# FAL65816_6567a.net
KiCad netlist of a schematic drawn in EAGLE
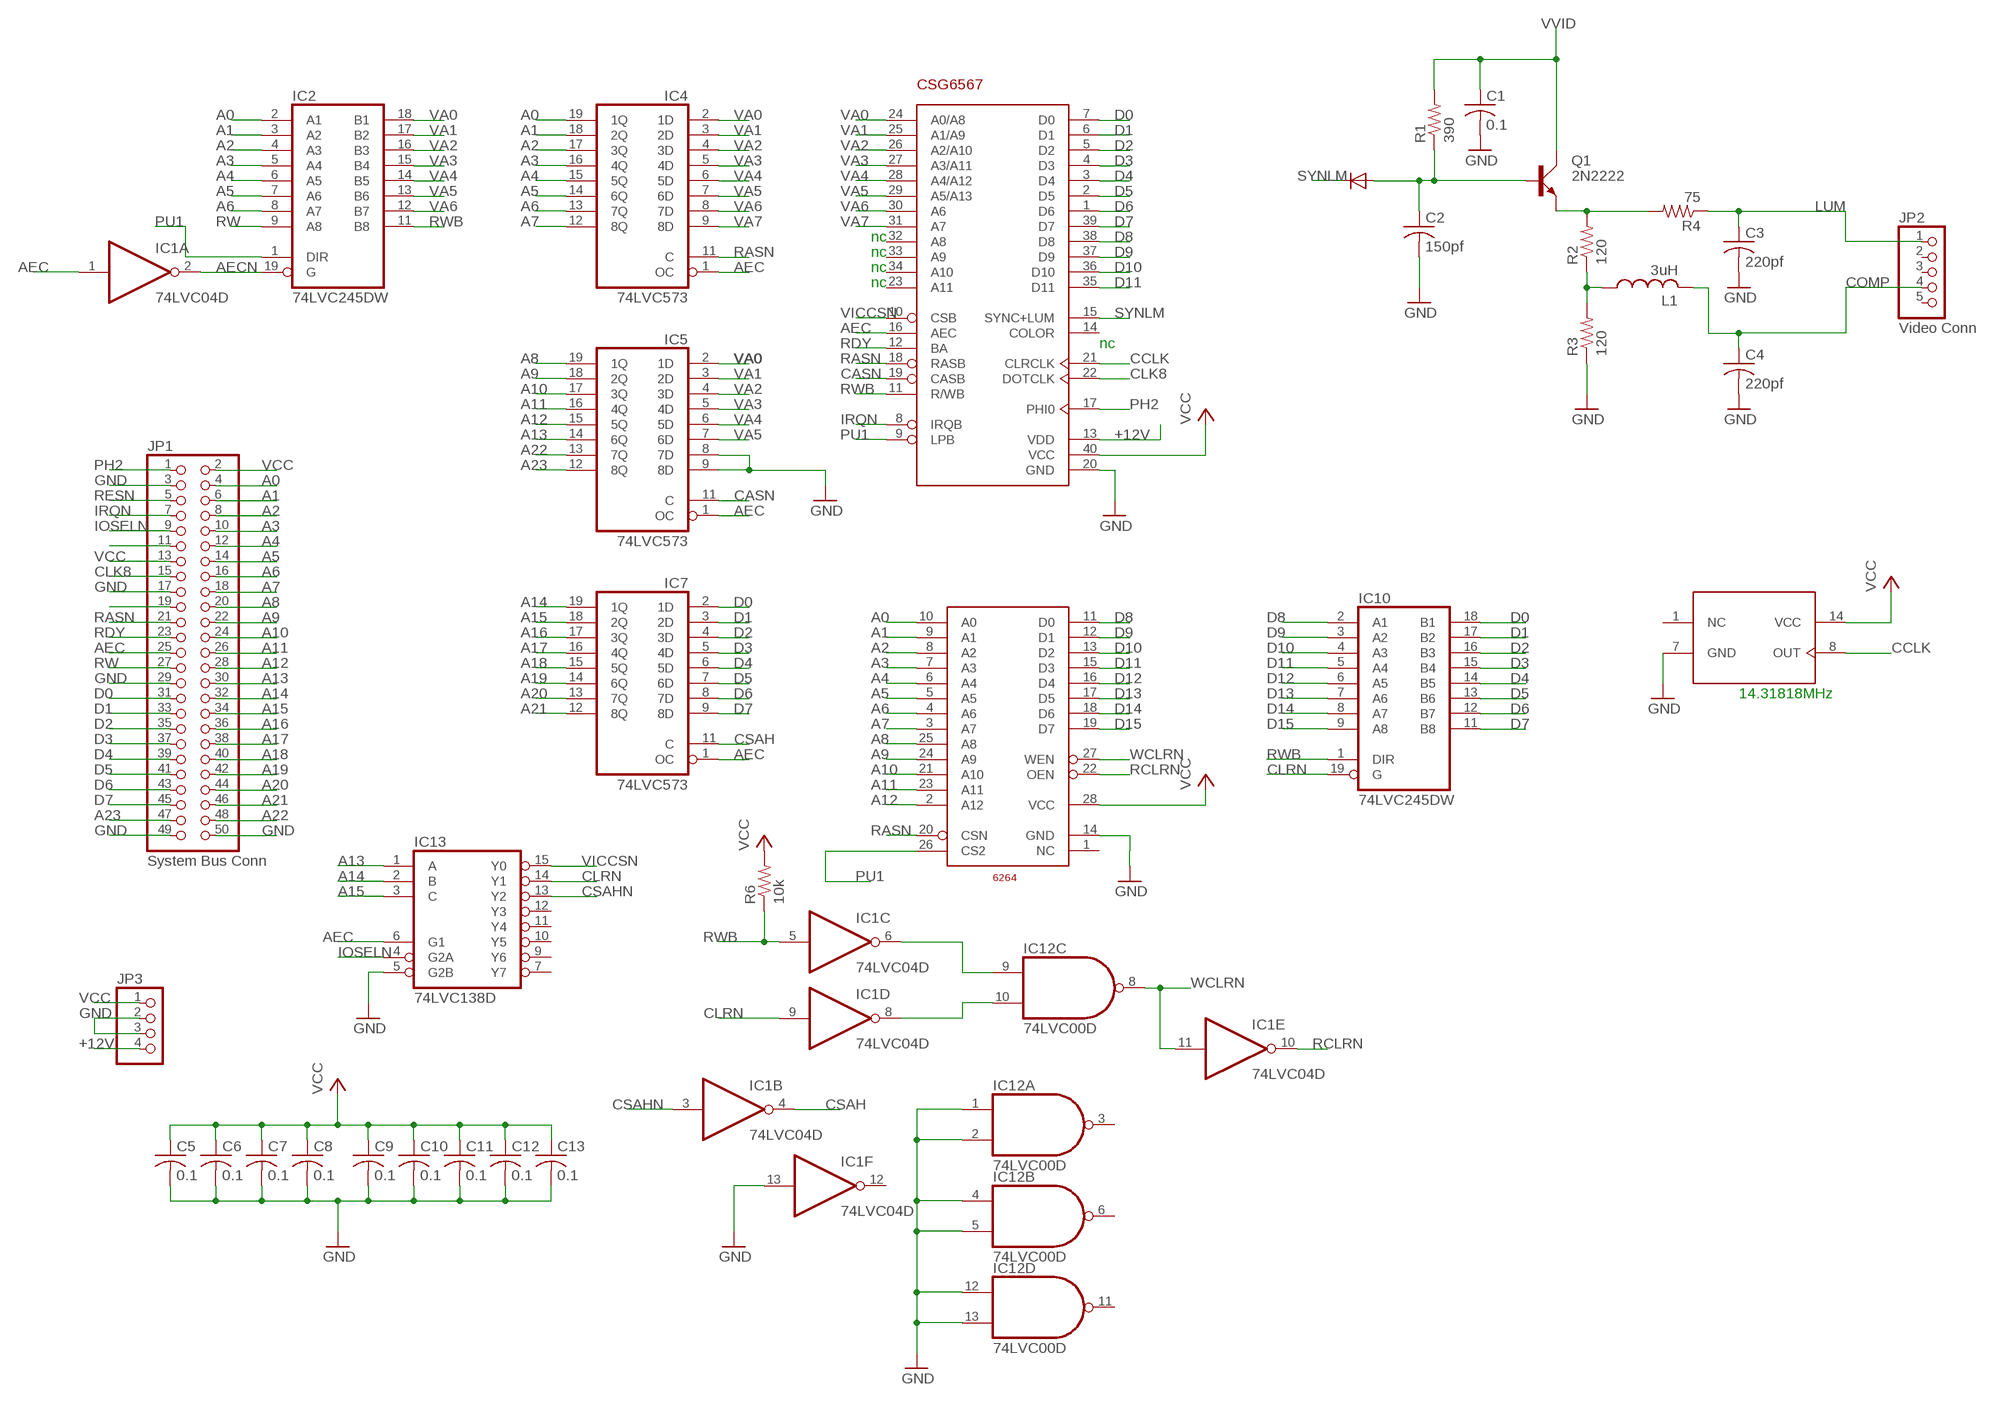
[diagram p0: schematic, sheet 1]

(export (version "E")
  (design (tool "Eeschema 10.0.6"))
  (components
    (comp (ref "C1")
      (value "0.1")
      (footprint "eagle-import:C050-024X044")
      (libsource (lib "eagle-import") (part "resistor_C-US050-024X044"))
    )
    (comp (ref "C2")
      (value "150pf")
      (footprint "eagle-import:C050-024X044")
      (libsource (lib "eagle-import") (part "C-US050-024X044"))
    )
    (comp (ref "C3")
      (value "220pf")
      (footprint "eagle-import:C050-024X044")
      (libsource (lib "eagle-import") (part "resistor_C-US050-024X044"))
    )
    (comp (ref "C4")
      (value "220pf")
      (footprint "eagle-import:C050-024X044")
      (libsource (lib "eagle-import") (part "resistor_C-US050-024X044"))
    )
    (comp (ref "C5")
      (value "0.1")
      (footprint "eagle-import:C050-024X044")
      (libsource (lib "eagle-import") (part "C-US050-024X044"))
    )
    (comp (ref "C6")
      (value "0.1")
      (footprint "eagle-import:C050-024X044")
      (libsource (lib "eagle-import") (part "C-US050-024X044"))
    )
    (comp (ref "C7")
      (value "0.1")
      (footprint "eagle-import:C050-024X044")
      (libsource (lib "eagle-import") (part "C-US050-024X044"))
    )
    (comp (ref "C8")
      (value "0.1")
      (footprint "eagle-import:C050-024X044")
      (libsource (lib "eagle-import") (part "C-US050-024X044"))
    )
    (comp (ref "C9")
      (value "0.1")
      (footprint "eagle-import:C050-024X044")
      (libsource (lib "eagle-import") (part "C-US050-024X044"))
    )
    (comp (ref "C10")
      (value "0.1")
      (footprint "eagle-import:C050-024X044")
      (libsource (lib "eagle-import") (part "C-US050-024X044"))
    )
    (comp (ref "C11")
      (value "0.1")
      (footprint "eagle-import:C050-024X044")
      (libsource (lib "eagle-import") (part "C-US050-024X044"))
    )
    (comp (ref "C12")
      (value "0.1")
      (footprint "eagle-import:C050-024X044")
      (libsource (lib "eagle-import") (part "C-US050-024X044"))
    )
    (comp (ref "C13")
      (value "0.1")
      (footprint "eagle-import:C050-024X044")
      (libsource (lib "eagle-import") (part "C-US050-024X044"))
    )
    (comp (ref "IC1")
      (value "74LVC04D")
      (footprint "eagle-import:SO14")
      (libsource (lib "eagle-import") (part "7404DLS"))
    )
    (comp (ref "IC2")
      (value "74LVC245DW")
      (footprint "eagle-import:SO20W")
      (libsource (lib "eagle-import") (part "FT74xx_74245DWLS"))
    )
    (comp (ref "IC4")
      (value "74LVC573")
      (footprint "eagle-import:SO20W")
      (libsource (lib "eagle-import") (part "74573LVC"))
    )
    (comp (ref "IC5")
      (value "74LVC573")
      (footprint "eagle-import:SO20W")
      (libsource (lib "eagle-import") (part "74573LVC"))
    )
    (comp (ref "IC7")
      (value "74LVC573")
      (footprint "eagle-import:SO20W")
      (libsource (lib "eagle-import") (part "74573LVC"))
    )
    (comp (ref "IC10")
      (value "74LVC245DW")
      (footprint "eagle-import:SO20W")
      (libsource (lib "eagle-import") (part "74245DWLS"))
    )
    (comp (ref "IC12")
      (value "74LVC00D")
      (footprint "eagle-import:SO14")
      (libsource (lib "eagle-import") (part "7400DLS"))
    )
    (comp (ref "IC13")
      (value "74LVC138D")
      (footprint "eagle-import:SO16")
      (libsource (lib "eagle-import") (part "74138DLS"))
    )
    (comp (ref "JP1")
      (value "System Bus Conn")
      (footprint "eagle-import:2X25_90")
      (libsource (lib "eagle-import") (part "PINHD-2X25/90"))
    )
    (comp (ref "JP2")
      (value "Video Conn")
      (footprint "eagle-import:1X05")
      (libsource (lib "eagle-import") (part "PINHD-1X5"))
    )
    (comp (ref "JP3")
      (value "PINHD-1X4/90")
      (footprint "eagle-import:1X04_90")
      (libsource (lib "eagle-import") (part "PINHD-1X4/90"))
    )
    (comp (ref "L1")
      (value "3uH")
      (footprint "eagle-import:0204_7")
      (libsource (lib "eagle-import") (part "L-US0204/7"))
    )
    (comp (ref "Q1")
      (value "2N2222")
      (footprint "eagle-import:TO18A")
      (libsource (lib "eagle-import") (part "2N2222"))
    )
    (comp (ref "R1")
      (value "390")
      (footprint "eagle-import:0204_7")
      (libsource (lib "eagle-import") (part "R-US_0204/7"))
    )
    (comp (ref "R2")
      (value "120")
      (footprint "eagle-import:0204_7")
      (libsource (lib "eagle-import") (part "R-US_0204/7"))
    )
    (comp (ref "R3")
      (value "120")
      (footprint "eagle-import:0204_7")
      (libsource (lib "eagle-import") (part "R-US_0204/7"))
    )
    (comp (ref "R4")
      (value "75")
      (footprint "eagle-import:0204_7")
      (libsource (lib "eagle-import") (part "R-US_0204/7"))
    )
    (comp (ref "R6")
      (value "10k")
      (footprint "eagle-import:0204_7")
      (libsource (lib "eagle-import") (part "R-US_0204/7"))
    )
    (comp (ref "U$1")
      (value "CSG6567")
      (footprint "eagle-import:DIP-40")
      (libsource (lib "eagle-import") (part "CSG6567"))
    )
    (comp (ref "U$3")
      (value "OSC14")
      (footprint "eagle-import:DIL14")
      (libsource (lib "eagle-import") (part "OSC14"))
    )
    (comp (ref "U$4")
      (value "6264")
      (footprint "eagle-import:DIL28-6")
      (libsource (lib "eagle-import") (part "6264"))
    )
  )
  (nets
    (net (code "1") (name "/+12V") (class "Default")
      (node (ref "JP3") (pin "4") (pinfunction "4_4") (pintype "passive"))
      (node (ref "U$1") (pin "13") (pinfunction "VDD_13") (pintype "power_in"))
    )
    (net (code "2") (name "/A0") (class "Default")
      (node (ref "IC2") (pin "2") (pinfunction "A1_2") (pintype "bidirectional"))
      (node (ref "IC4") (pin "19") (pinfunction "1Q_19") (pintype "tri_state"))
      (node (ref "JP1") (pin "4") (pinfunction "4_4") (pintype "passive"))
      (node (ref "U$4") (pin "10") (pinfunction "A0_10") (pintype "input"))
    )
    (net (code "3") (name "/A1") (class "Default")
      (node (ref "IC2") (pin "3") (pinfunction "A2_3") (pintype "bidirectional"))
      (node (ref "IC4") (pin "18") (pinfunction "2Q_18") (pintype "tri_state"))
      (node (ref "JP1") (pin "6") (pinfunction "6_6") (pintype "passive"))
      (node (ref "U$4") (pin "9") (pinfunction "A1_9") (pintype "input"))
    )
    (net (code "4") (name "/A2") (class "Default")
      (node (ref "IC2") (pin "4") (pinfunction "A3_4") (pintype "bidirectional"))
      (node (ref "IC4") (pin "17") (pinfunction "3Q_17") (pintype "tri_state"))
      (node (ref "JP1") (pin "8") (pinfunction "8_8") (pintype "passive"))
      (node (ref "U$4") (pin "8") (pinfunction "A2_8") (pintype "input"))
    )
    (net (code "5") (name "/A3") (class "Default")
      (node (ref "IC2") (pin "5") (pinfunction "A4_5") (pintype "bidirectional"))
      (node (ref "IC4") (pin "16") (pinfunction "4Q_16") (pintype "tri_state"))
      (node (ref "JP1") (pin "10") (pinfunction "10_10") (pintype "passive"))
      (node (ref "U$4") (pin "7") (pinfunction "A3_7") (pintype "input"))
    )
    (net (code "6") (name "/A4") (class "Default")
      (node (ref "IC2") (pin "6") (pinfunction "A5_6") (pintype "bidirectional"))
      (node (ref "IC4") (pin "15") (pinfunction "5Q_15") (pintype "tri_state"))
      (node (ref "JP1") (pin "12") (pinfunction "12_12") (pintype "passive"))
      (node (ref "U$4") (pin "6") (pinfunction "A4_6") (pintype "input"))
    )
    (net (code "7") (name "/A5") (class "Default")
      (node (ref "IC2") (pin "7") (pinfunction "A6_7") (pintype "bidirectional"))
      (node (ref "IC4") (pin "14") (pinfunction "6Q_14") (pintype "tri_state"))
      (node (ref "JP1") (pin "14") (pinfunction "14_14") (pintype "passive"))
      (node (ref "U$4") (pin "5") (pinfunction "A5_5") (pintype "input"))
    )
    (net (code "8") (name "/A6") (class "Default")
      (node (ref "IC2") (pin "8") (pinfunction "A7_8") (pintype "bidirectional"))
      (node (ref "IC4") (pin "13") (pinfunction "7Q_13") (pintype "tri_state"))
      (node (ref "JP1") (pin "16") (pinfunction "16_16") (pintype "passive"))
      (node (ref "U$4") (pin "4") (pinfunction "A6_4") (pintype "input"))
    )
    (net (code "9") (name "/A7") (class "Default")
      (node (ref "IC4") (pin "12") (pinfunction "8Q_12") (pintype "tri_state"))
      (node (ref "JP1") (pin "18") (pinfunction "18_18") (pintype "passive"))
      (node (ref "U$4") (pin "3") (pinfunction "A7_3") (pintype "input"))
    )
    (net (code "10") (name "/A8") (class "Default")
      (node (ref "IC5") (pin "19") (pinfunction "1Q_19") (pintype "tri_state"))
      (node (ref "JP1") (pin "20") (pinfunction "20_20") (pintype "passive"))
      (node (ref "U$4") (pin "25") (pinfunction "A8_25") (pintype "input"))
    )
    (net (code "11") (name "/A9") (class "Default")
      (node (ref "IC5") (pin "18") (pinfunction "2Q_18") (pintype "tri_state"))
      (node (ref "JP1") (pin "22") (pinfunction "22_22") (pintype "passive"))
      (node (ref "U$4") (pin "24") (pinfunction "A9_24") (pintype "input"))
    )
    (net (code "12") (name "/A10") (class "Default")
      (node (ref "IC5") (pin "17") (pinfunction "3Q_17") (pintype "tri_state"))
      (node (ref "JP1") (pin "24") (pinfunction "24_24") (pintype "passive"))
      (node (ref "U$4") (pin "21") (pinfunction "A10_21") (pintype "input"))
    )
    (net (code "13") (name "/A11") (class "Default")
      (node (ref "IC5") (pin "16") (pinfunction "4Q_16") (pintype "tri_state"))
      (node (ref "JP1") (pin "26") (pinfunction "26_26") (pintype "passive"))
      (node (ref "U$4") (pin "23") (pinfunction "A11_23") (pintype "input"))
    )
    (net (code "14") (name "/A12") (class "Default")
      (node (ref "IC5") (pin "15") (pinfunction "5Q_15") (pintype "tri_state"))
      (node (ref "JP1") (pin "28") (pinfunction "28_28") (pintype "passive"))
      (node (ref "U$4") (pin "2") (pinfunction "A12_2") (pintype "input"))
    )
    (net (code "15") (name "/A13") (class "Default")
      (node (ref "IC13") (pin "1") (pinfunction "A_1") (pintype "input"))
      (node (ref "IC5") (pin "14") (pinfunction "6Q_14") (pintype "tri_state"))
      (node (ref "JP1") (pin "30") (pinfunction "30_30") (pintype "passive"))
    )
    (net (code "16") (name "/A14") (class "Default")
      (node (ref "IC13") (pin "2") (pinfunction "B_2") (pintype "input"))
      (node (ref "IC7") (pin "19") (pinfunction "1Q_19") (pintype "tri_state"))
      (node (ref "JP1") (pin "32") (pinfunction "32_32") (pintype "passive"))
    )
    (net (code "17") (name "/A15") (class "Default")
      (node (ref "IC13") (pin "3") (pinfunction "C_3") (pintype "input"))
      (node (ref "IC7") (pin "18") (pinfunction "2Q_18") (pintype "tri_state"))
      (node (ref "JP1") (pin "34") (pinfunction "34_34") (pintype "passive"))
    )
    (net (code "18") (name "/A16") (class "Default")
      (node (ref "IC7") (pin "17") (pinfunction "3Q_17") (pintype "tri_state"))
      (node (ref "JP1") (pin "36") (pinfunction "36_36") (pintype "passive"))
    )
    (net (code "19") (name "/A17") (class "Default")
      (node (ref "IC7") (pin "16") (pinfunction "4Q_16") (pintype "tri_state"))
      (node (ref "JP1") (pin "38") (pinfunction "38_38") (pintype "passive"))
    )
    (net (code "20") (name "/A18") (class "Default")
      (node (ref "IC7") (pin "15") (pinfunction "5Q_15") (pintype "tri_state"))
      (node (ref "JP1") (pin "40") (pinfunction "40_40") (pintype "passive"))
    )
    (net (code "21") (name "/A19") (class "Default")
      (node (ref "IC7") (pin "14") (pinfunction "6Q_14") (pintype "tri_state"))
      (node (ref "JP1") (pin "42") (pinfunction "42_42") (pintype "passive"))
    )
    (net (code "22") (name "/A20") (class "Default")
      (node (ref "IC7") (pin "13") (pinfunction "7Q_13") (pintype "tri_state"))
      (node (ref "JP1") (pin "44") (pinfunction "44_44") (pintype "passive"))
    )
    (net (code "23") (name "/A21") (class "Default")
      (node (ref "IC7") (pin "12") (pinfunction "8Q_12") (pintype "tri_state"))
      (node (ref "JP1") (pin "46") (pinfunction "46_46") (pintype "passive"))
    )
    (net (code "24") (name "/A22") (class "Default")
      (node (ref "IC5") (pin "13") (pinfunction "7Q_13") (pintype "tri_state"))
      (node (ref "JP1") (pin "48") (pinfunction "48_48") (pintype "passive"))
    )
    (net (code "25") (name "/A23") (class "Default")
      (node (ref "IC5") (pin "12") (pinfunction "8Q_12") (pintype "tri_state"))
      (node (ref "JP1") (pin "47") (pinfunction "47_47") (pintype "passive"))
    )
    (net (code "26") (name "/AEC") (class "Default")
      (node (ref "IC1") (pin "1") (pinfunction "I_1") (pintype "input"))
      (node (ref "IC13") (pin "6") (pinfunction "G1_6") (pintype "input"))
      (node (ref "IC4") (pin "1") (pinfunction "OC_1") (pintype "input"))
      (node (ref "IC5") (pin "1") (pinfunction "OC_1") (pintype "input"))
      (node (ref "IC7") (pin "1") (pinfunction "OC_1") (pintype "input"))
      (node (ref "JP1") (pin "25") (pinfunction "25_25") (pintype "passive"))
      (node (ref "U$1") (pin "16") (pinfunction "AEC_16") (pintype "output"))
    )
    (net (code "27") (name "/AECN") (class "Default")
      (node (ref "IC1") (pin "2") (pinfunction "O_2") (pintype "output"))
      (node (ref "IC2") (pin "19") (pinfunction "G_19") (pintype "input"))
    )
    (net (code "28") (name "/CASN") (class "Default")
      (node (ref "IC5") (pin "11") (pinfunction "C_11") (pintype "input"))
      (node (ref "U$1") (pin "19") (pinfunction "CASB_19") (pintype "output"))
    )
    (net (code "29") (name "/CCLK") (class "Default")
      (node (ref "U$1") (pin "21") (pinfunction "CLRCLK_21") (pintype "input"))
      (node (ref "U$3") (pin "8") (pinfunction "OUT_8") (pintype "output"))
    )
    (net (code "30") (name "/CLK8") (class "Default")
      (node (ref "JP1") (pin "15") (pinfunction "15_15") (pintype "passive"))
      (node (ref "U$1") (pin "22") (pinfunction "DOTCLK_22") (pintype "input"))
    )
    (net (code "31") (name "/CLRN") (class "Default")
      (node (ref "IC1") (pin "9") (pinfunction "I_9") (pintype "input"))
      (node (ref "IC10") (pin "19") (pinfunction "G_19") (pintype "input"))
      (node (ref "IC13") (pin "14") (pinfunction "Y1_14") (pintype "output"))
    )
    (net (code "32") (name "/COMP") (class "Default")
      (node (ref "C4") (pin "1") (pinfunction "1_1") (pintype "passive"))
      (node (ref "JP2") (pin "4") (pinfunction "4_4") (pintype "passive"))
      (node (ref "L1") (pin "2") (pinfunction "2_2") (pintype "passive"))
    )
    (net (code "33") (name "/CSAH") (class "Default")
      (node (ref "IC1") (pin "4") (pinfunction "O_4") (pintype "output"))
      (node (ref "IC7") (pin "11") (pinfunction "C_11") (pintype "input"))
    )
    (net (code "34") (name "/CSAHN") (class "Default")
      (node (ref "IC1") (pin "3") (pinfunction "I_3") (pintype "input"))
      (node (ref "IC13") (pin "13") (pinfunction "Y2_13") (pintype "output"))
    )
    (net (code "35") (name "/D0") (class "Default")
      (node (ref "IC10") (pin "18") (pinfunction "B1_18") (pintype "bidirectional"))
      (node (ref "IC7") (pin "2") (pinfunction "1D_2") (pintype "input"))
      (node (ref "JP1") (pin "31") (pinfunction "31_31") (pintype "passive"))
      (node (ref "U$1") (pin "7") (pinfunction "D0_7") (pintype "bidirectional"))
    )
    (net (code "36") (name "/D1") (class "Default")
      (node (ref "IC10") (pin "17") (pinfunction "B2_17") (pintype "bidirectional"))
      (node (ref "IC7") (pin "3") (pinfunction "2D_3") (pintype "input"))
      (node (ref "JP1") (pin "33") (pinfunction "33_33") (pintype "passive"))
      (node (ref "U$1") (pin "6") (pinfunction "D1_6") (pintype "bidirectional"))
    )
    (net (code "37") (name "/D2") (class "Default")
      (node (ref "IC10") (pin "16") (pinfunction "B3_16") (pintype "bidirectional"))
      (node (ref "IC7") (pin "4") (pinfunction "3D_4") (pintype "input"))
      (node (ref "JP1") (pin "35") (pinfunction "35_35") (pintype "passive"))
      (node (ref "U$1") (pin "5") (pinfunction "D2_5") (pintype "bidirectional"))
    )
    (net (code "38") (name "/D3") (class "Default")
      (node (ref "IC10") (pin "15") (pinfunction "B4_15") (pintype "bidirectional"))
      (node (ref "IC7") (pin "5") (pinfunction "4D_5") (pintype "input"))
      (node (ref "JP1") (pin "37") (pinfunction "37_37") (pintype "passive"))
      (node (ref "U$1") (pin "4") (pinfunction "D3_4") (pintype "bidirectional"))
    )
    (net (code "39") (name "/D4") (class "Default")
      (node (ref "IC10") (pin "14") (pinfunction "B5_14") (pintype "bidirectional"))
      (node (ref "IC7") (pin "6") (pinfunction "5D_6") (pintype "input"))
      (node (ref "JP1") (pin "39") (pinfunction "39_39") (pintype "passive"))
      (node (ref "U$1") (pin "3") (pinfunction "D4_3") (pintype "bidirectional"))
    )
    (net (code "40") (name "/D5") (class "Default")
      (node (ref "IC10") (pin "13") (pinfunction "B6_13") (pintype "bidirectional"))
      (node (ref "IC7") (pin "7") (pinfunction "6D_7") (pintype "input"))
      (node (ref "JP1") (pin "41") (pinfunction "41_41") (pintype "passive"))
      (node (ref "U$1") (pin "2") (pinfunction "D5_2") (pintype "bidirectional"))
    )
    (net (code "41") (name "/D6") (class "Default")
      (node (ref "IC10") (pin "12") (pinfunction "B7_12") (pintype "bidirectional"))
      (node (ref "IC7") (pin "8") (pinfunction "7D_8") (pintype "input"))
      (node (ref "JP1") (pin "43") (pinfunction "43_43") (pintype "passive"))
      (node (ref "U$1") (pin "1") (pinfunction "D6_1") (pintype "bidirectional"))
    )
    (net (code "42") (name "/D7") (class "Default")
      (node (ref "IC10") (pin "11") (pinfunction "B8_11") (pintype "bidirectional"))
      (node (ref "IC7") (pin "9") (pinfunction "8D_9") (pintype "input"))
      (node (ref "JP1") (pin "45") (pinfunction "45_45") (pintype "passive"))
      (node (ref "U$1") (pin "39") (pinfunction "D7_39") (pintype "bidirectional"))
    )
    (net (code "43") (name "/D8") (class "Default")
      (node (ref "IC10") (pin "2") (pinfunction "A1_2") (pintype "bidirectional"))
      (node (ref "U$1") (pin "38") (pinfunction "D8_38") (pintype "input"))
      (node (ref "U$4") (pin "11") (pinfunction "D0_11") (pintype "bidirectional"))
    )
    (net (code "44") (name "/D9") (class "Default")
      (node (ref "IC10") (pin "3") (pinfunction "A2_3") (pintype "bidirectional"))
      (node (ref "U$1") (pin "37") (pinfunction "D9_37") (pintype "input"))
      (node (ref "U$4") (pin "12") (pinfunction "D1_12") (pintype "bidirectional"))
    )
    (net (code "45") (name "/D10") (class "Default")
      (node (ref "IC10") (pin "4") (pinfunction "A3_4") (pintype "bidirectional"))
      (node (ref "U$1") (pin "36") (pinfunction "D10_36") (pintype "input"))
      (node (ref "U$4") (pin "13") (pinfunction "D2_13") (pintype "bidirectional"))
    )
    (net (code "46") (name "/D11") (class "Default")
      (node (ref "IC10") (pin "5") (pinfunction "A4_5") (pintype "bidirectional"))
      (node (ref "U$1") (pin "35") (pinfunction "D11_35") (pintype "input"))
      (node (ref "U$4") (pin "15") (pinfunction "D3_15") (pintype "bidirectional"))
    )
    (net (code "47") (name "/D12") (class "Default")
      (node (ref "IC10") (pin "6") (pinfunction "A5_6") (pintype "bidirectional"))
      (node (ref "U$4") (pin "16") (pinfunction "D4_16") (pintype "bidirectional"))
    )
    (net (code "48") (name "/D13") (class "Default")
      (node (ref "IC10") (pin "7") (pinfunction "A6_7") (pintype "bidirectional"))
      (node (ref "U$4") (pin "17") (pinfunction "D5_17") (pintype "bidirectional"))
    )
    (net (code "49") (name "/D14") (class "Default")
      (node (ref "IC10") (pin "8") (pinfunction "A7_8") (pintype "bidirectional"))
      (node (ref "U$4") (pin "18") (pinfunction "D6_18") (pintype "bidirectional"))
    )
    (net (code "50") (name "/D15") (class "Default")
      (node (ref "IC10") (pin "9") (pinfunction "A8_9") (pintype "bidirectional"))
      (node (ref "U$4") (pin "19") (pinfunction "D7_19") (pintype "bidirectional"))
    )
    (net (code "51") (name "/IOSELN") (class "Default")
      (node (ref "IC13") (pin "4") (pinfunction "G2A_4") (pintype "input"))
      (node (ref "JP1") (pin "9") (pinfunction "9_9") (pintype "passive"))
    )
    (net (code "52") (name "/IRQN") (class "Default")
      (node (ref "JP1") (pin "7") (pinfunction "7_7") (pintype "passive"))
      (node (ref "U$1") (pin "8") (pinfunction "IRQB_8") (pintype "open_collector"))
    )
    (net (code "53") (name "/LUM") (class "Default")
      (node (ref "C3") (pin "1") (pinfunction "1_1") (pintype "passive"))
      (node (ref "JP2") (pin "1") (pinfunction "1_1") (pintype "passive"))
      (node (ref "R4") (pin "1") (pinfunction "1_1") (pintype "passive"))
    )
    (net (code "54") (name "/PH2") (class "Default")
      (node (ref "JP1") (pin "1") (pinfunction "1_1") (pintype "passive"))
      (node (ref "U$1") (pin "17") (pinfunction "PHI0_17") (pintype "output"))
    )
    (net (code "55") (name "/PU1") (class "Default")
      (node (ref "IC2") (pin "1") (pinfunction "DIR_1") (pintype "input"))
      (node (ref "U$1") (pin "9") (pinfunction "LPB_9") (pintype "input"))
      (node (ref "U$4") (pin "26") (pinfunction "CS2_26") (pintype "input"))
    )
    (net (code "56") (name "/RASN") (class "Default")
      (node (ref "IC4") (pin "11") (pinfunction "C_11") (pintype "input"))
      (node (ref "JP1") (pin "21") (pinfunction "21_21") (pintype "passive"))
      (node (ref "U$1") (pin "18") (pinfunction "RASB_18") (pintype "output"))
      (node (ref "U$4") (pin "20") (pinfunction "CSN_20") (pintype "input"))
    )
    (net (code "57") (name "/RCLRN") (class "Default")
      (node (ref "IC1") (pin "10") (pinfunction "O_10") (pintype "output"))
      (node (ref "U$4") (pin "22") (pinfunction "OEN_22") (pintype "input"))
    )
    (net (code "58") (name "/RDY") (class "Default")
      (node (ref "JP1") (pin "23") (pinfunction "23_23") (pintype "passive"))
      (node (ref "U$1") (pin "12") (pinfunction "BA_12") (pintype "output"))
    )
    (net (code "59") (name "/RESN") (class "Default")
      (node (ref "JP1") (pin "5") (pinfunction "5_5") (pintype "passive"))
    )
    (net (code "60") (name "/RW") (class "Default")
      (node (ref "IC2") (pin "9") (pinfunction "A8_9") (pintype "bidirectional"))
      (node (ref "JP1") (pin "27") (pinfunction "27_27") (pintype "passive"))
    )
    (net (code "61") (name "/RWB") (class "Default")
      (node (ref "IC1") (pin "5") (pinfunction "I_5") (pintype "input"))
      (node (ref "IC10") (pin "1") (pinfunction "DIR_1") (pintype "input"))
      (node (ref "IC2") (pin "11") (pinfunction "B8_11") (pintype "bidirectional"))
      (node (ref "R6") (pin "1") (pinfunction "1_1") (pintype "passive"))
      (node (ref "U$1") (pin "11") (pinfunction "R/WB_11") (pintype "input"))
    )
    (net (code "62") (name "/SYNLM") (class "Default")
      (node (ref "U$1") (pin "15") (pinfunction "SYNC+LUM_15") (pintype "output"))
    )
    (net (code "63") (name "/VA0") (class "Default")
      (node (ref "IC2") (pin "18") (pinfunction "B1_18") (pintype "bidirectional"))
      (node (ref "IC4") (pin "2") (pinfunction "1D_2") (pintype "input"))
      (node (ref "IC5") (pin "2") (pinfunction "1D_2") (pintype "input"))
      (node (ref "U$1") (pin "24") (pinfunction "A0/A8_24") (pintype "bidirectional"))
    )
    (net (code "64") (name "/VA1") (class "Default")
      (node (ref "IC2") (pin "17") (pinfunction "B2_17") (pintype "bidirectional"))
      (node (ref "IC4") (pin "3") (pinfunction "2D_3") (pintype "input"))
      (node (ref "IC5") (pin "3") (pinfunction "2D_3") (pintype "input"))
      (node (ref "U$1") (pin "25") (pinfunction "A1/A9_25") (pintype "bidirectional"))
    )
    (net (code "65") (name "/VA2") (class "Default")
      (node (ref "IC2") (pin "16") (pinfunction "B3_16") (pintype "bidirectional"))
      (node (ref "IC4") (pin "4") (pinfunction "3D_4") (pintype "input"))
      (node (ref "IC5") (pin "4") (pinfunction "3D_4") (pintype "input"))
      (node (ref "U$1") (pin "26") (pinfunction "A2/A10_26") (pintype "bidirectional"))
    )
    (net (code "66") (name "/VA3") (class "Default")
      (node (ref "IC2") (pin "15") (pinfunction "B4_15") (pintype "bidirectional"))
      (node (ref "IC4") (pin "5") (pinfunction "4D_5") (pintype "input"))
      (node (ref "IC5") (pin "5") (pinfunction "4D_5") (pintype "input"))
      (node (ref "U$1") (pin "27") (pinfunction "A3/A11_27") (pintype "bidirectional"))
    )
    (net (code "67") (name "/VA4") (class "Default")
      (node (ref "IC2") (pin "14") (pinfunction "B5_14") (pintype "bidirectional"))
      (node (ref "IC4") (pin "6") (pinfunction "5D_6") (pintype "input"))
      (node (ref "IC5") (pin "6") (pinfunction "5D_6") (pintype "input"))
      (node (ref "U$1") (pin "28") (pinfunction "A4/A12_28") (pintype "bidirectional"))
    )
    (net (code "68") (name "/VA5") (class "Default")
      (node (ref "IC2") (pin "13") (pinfunction "B6_13") (pintype "bidirectional"))
      (node (ref "IC4") (pin "7") (pinfunction "6D_7") (pintype "input"))
      (node (ref "IC5") (pin "7") (pinfunction "6D_7") (pintype "input"))
      (node (ref "U$1") (pin "29") (pinfunction "A5/A13_29") (pintype "bidirectional"))
    )
    (net (code "69") (name "/VA6") (class "Default")
      (node (ref "IC2") (pin "12") (pinfunction "B7_12") (pintype "bidirectional"))
      (node (ref "IC4") (pin "8") (pinfunction "7D_8") (pintype "input"))
      (node (ref "U$1") (pin "30") (pinfunction "A6_30") (pintype "bidirectional"))
    )
    (net (code "70") (name "/VA7") (class "Default")
      (node (ref "IC4") (pin "9") (pinfunction "8D_9") (pintype "input"))
      (node (ref "U$1") (pin "31") (pinfunction "A7_31") (pintype "bidirectional"))
    )
    (net (code "71") (name "/VICCSN") (class "Default")
      (node (ref "IC13") (pin "15") (pinfunction "Y0_15") (pintype "output"))
      (node (ref "U$1") (pin "10") (pinfunction "CSB_10") (pintype "input"))
    )
    (net (code "72") (name "/VVID") (class "Default")
      (node (ref "C1") (pin "1") (pinfunction "1_1") (pintype "passive"))
      (node (ref "Q1") (pin "C") (pinfunction "C_C") (pintype "passive"))
      (node (ref "R1") (pin "2") (pinfunction "2_2") (pintype "passive"))
    )
    (net (code "73") (name "/WCLRN") (class "Default")
      (node (ref "IC1") (pin "11") (pinfunction "I_11") (pintype "input"))
      (node (ref "IC12") (pin "8") (pinfunction "O_8") (pintype "output"))
      (node (ref "U$4") (pin "27") (pinfunction "WEN_27") (pintype "input"))
    )
    (net (code "74") (name "GND") (class "Default")
      (node (ref "C1") (pin "2") (pinfunction "2_2") (pintype "passive"))
      (node (ref "C10") (pin "2") (pinfunction "2_2") (pintype "passive"))
      (node (ref "C11") (pin "2") (pinfunction "2_2") (pintype "passive"))
      (node (ref "C12") (pin "2") (pinfunction "2_2") (pintype "passive"))
      (node (ref "C13") (pin "2") (pinfunction "2_2") (pintype "passive"))
      (node (ref "C2") (pin "2") (pinfunction "2_2") (pintype "passive"))
      (node (ref "C3") (pin "2") (pinfunction "2_2") (pintype "passive"))
      (node (ref "C4") (pin "2") (pinfunction "2_2") (pintype "passive"))
      (node (ref "C5") (pin "2") (pinfunction "2_2") (pintype "passive"))
      (node (ref "C6") (pin "2") (pinfunction "2_2") (pintype "passive"))
      (node (ref "C7") (pin "2") (pinfunction "2_2") (pintype "passive"))
      (node (ref "C8") (pin "2") (pinfunction "2_2") (pintype "passive"))
      (node (ref "C9") (pin "2") (pinfunction "2_2") (pintype "passive"))
      (node (ref "IC1") (pin "13") (pinfunction "I_13") (pintype "input"))
      (node (ref "IC12") (pin "1") (pinfunction "I0_1") (pintype "input"))
      (node (ref "IC12") (pin "12") (pinfunction "I0_12") (pintype "input"))
      (node (ref "IC12") (pin "13") (pinfunction "I1_13") (pintype "input"))
      (node (ref "IC12") (pin "2") (pinfunction "I1_2") (pintype "input"))
      (node (ref "IC12") (pin "4") (pinfunction "I0_4") (pintype "input"))
      (node (ref "IC12") (pin "5") (pinfunction "I1_5") (pintype "input"))
      (node (ref "IC13") (pin "5") (pinfunction "G2B_5") (pintype "input"))
      (node (ref "IC5") (pin "8") (pinfunction "7D_8") (pintype "input"))
      (node (ref "IC5") (pin "9") (pinfunction "8D_9") (pintype "input"))
      (node (ref "JP1") (pin "17") (pinfunction "17_17") (pintype "passive"))
      (node (ref "JP1") (pin "29") (pinfunction "29_29") (pintype "passive"))
      (node (ref "JP1") (pin "3") (pinfunction "3_3") (pintype "passive"))
      (node (ref "JP1") (pin "49") (pinfunction "49_49") (pintype "passive"))
      (node (ref "JP1") (pin "50") (pinfunction "50_50") (pintype "passive"))
      (node (ref "JP3") (pin "2") (pinfunction "2_2") (pintype "passive"))
      (node (ref "JP3") (pin "3") (pinfunction "3_3") (pintype "passive"))
      (node (ref "R3") (pin "1") (pinfunction "1_1") (pintype "passive"))
      (node (ref "U$1") (pin "20") (pinfunction "GND_20") (pintype "power_in"))
      (node (ref "U$3") (pin "7") (pinfunction "GND_7") (pintype "power_in"))
      (node (ref "U$4") (pin "14") (pinfunction "GND_14") (pintype "power_in"))
    )
    (net (code "75") (name "Net-(C2-Pad1)") (class "Default")
      (node (ref "C2") (pin "1") (pinfunction "1_1") (pintype "passive"))
      (node (ref "Q1") (pin "B") (pinfunction "B_B") (pintype "passive"))
      (node (ref "R1") (pin "1") (pinfunction "1_1") (pintype "passive"))
    )
    (net (code "76") (name "Net-(IC12C-I0)") (class "Default")
      (node (ref "IC1") (pin "6") (pinfunction "O_6") (pintype "output"))
      (node (ref "IC12") (pin "9") (pinfunction "I0_9") (pintype "input"))
    )
    (net (code "77") (name "Net-(IC12C-I1)") (class "Default")
      (node (ref "IC1") (pin "8") (pinfunction "O_8") (pintype "output"))
      (node (ref "IC12") (pin "10") (pinfunction "I1_10") (pintype "input"))
    )
    (net (code "78") (name "Net-(L1-Pad1)") (class "Default")
      (node (ref "L1") (pin "1") (pinfunction "1_1") (pintype "passive"))
      (node (ref "R2") (pin "1") (pinfunction "1_1") (pintype "passive"))
      (node (ref "R3") (pin "2") (pinfunction "2_2") (pintype "passive"))
    )
    (net (code "79") (name "Net-(Q1-PadE)") (class "Default")
      (node (ref "Q1") (pin "E") (pinfunction "E_E") (pintype "passive"))
      (node (ref "R2") (pin "2") (pinfunction "2_2") (pintype "passive"))
      (node (ref "R4") (pin "2") (pinfunction "2_2") (pintype "passive"))
    )
    (net (code "80") (name "VCC") (class "Default")
      (node (ref "C10") (pin "1") (pinfunction "1_1") (pintype "passive"))
      (node (ref "C11") (pin "1") (pinfunction "1_1") (pintype "passive"))
      (node (ref "C12") (pin "1") (pinfunction "1_1") (pintype "passive"))
      (node (ref "C13") (pin "1") (pinfunction "1_1") (pintype "passive"))
      (node (ref "C5") (pin "1") (pinfunction "1_1") (pintype "passive"))
      (node (ref "C6") (pin "1") (pinfunction "1_1") (pintype "passive"))
      (node (ref "C7") (pin "1") (pinfunction "1_1") (pintype "passive"))
      (node (ref "C8") (pin "1") (pinfunction "1_1") (pintype "passive"))
      (node (ref "C9") (pin "1") (pinfunction "1_1") (pintype "passive"))
      (node (ref "JP1") (pin "13") (pinfunction "13_13") (pintype "passive"))
      (node (ref "JP1") (pin "2") (pinfunction "2_2") (pintype "passive"))
      (node (ref "JP3") (pin "1") (pinfunction "1_1") (pintype "passive"))
      (node (ref "R6") (pin "2") (pinfunction "2_2") (pintype "passive"))
      (node (ref "U$1") (pin "40") (pinfunction "VCC_40") (pintype "power_in"))
      (node (ref "U$3") (pin "14") (pinfunction "VCC_14") (pintype "power_in"))
      (node (ref "U$4") (pin "28") (pinfunction "VCC_28") (pintype "power_in"))
    )
    (net (code "81") (name "unconnected-(IC1F-O-Pad12)") (class "Default")
      (node (ref "IC1") (pin "12") (pinfunction "O_12") (pintype "output"))
    )
    (net (code "82") (name "unconnected-(IC12A-O-Pad3)") (class "Default")
      (node (ref "IC12") (pin "3") (pinfunction "O_3") (pintype "output"))
    )
    (net (code "83") (name "unconnected-(IC12B-O-Pad6)") (class "Default")
      (node (ref "IC12") (pin "6") (pinfunction "O_6") (pintype "output"))
    )
    (net (code "84") (name "unconnected-(IC12D-O-Pad11)") (class "Default")
      (node (ref "IC12") (pin "11") (pinfunction "O_11") (pintype "output"))
    )
    (net (code "85") (name "unconnected-(IC13A-Y3-Pad12)") (class "Default")
      (node (ref "IC13") (pin "12") (pinfunction "Y3_12") (pintype "output"))
    )
    (net (code "86") (name "unconnected-(IC13A-Y4-Pad11)") (class "Default")
      (node (ref "IC13") (pin "11") (pinfunction "Y4_11") (pintype "output"))
    )
    (net (code "87") (name "unconnected-(IC13A-Y5-Pad10)") (class "Default")
      (node (ref "IC13") (pin "10") (pinfunction "Y5_10") (pintype "output"))
    )
    (net (code "88") (name "unconnected-(IC13A-Y6-Pad9)") (class "Default")
      (node (ref "IC13") (pin "9") (pinfunction "Y6_9") (pintype "output"))
    )
    (net (code "89") (name "unconnected-(IC13A-Y7-Pad7)") (class "Default")
      (node (ref "IC13") (pin "7") (pinfunction "Y7_7") (pintype "output"))
    )
    (net (code "90") (name "unconnected-(JP1-Pad11)") (class "Default")
      (node (ref "JP1") (pin "11") (pinfunction "11_11") (pintype "passive"))
    )
    (net (code "91") (name "unconnected-(JP1-Pad19)") (class "Default")
      (node (ref "JP1") (pin "19") (pinfunction "19_19") (pintype "passive"))
    )
    (net (code "92") (name "unconnected-(JP2-Pad2)") (class "Default")
      (node (ref "JP2") (pin "2") (pinfunction "2_2") (pintype "passive"))
    )
    (net (code "93") (name "unconnected-(JP2-Pad3)") (class "Default")
      (node (ref "JP2") (pin "3") (pinfunction "3_3") (pintype "passive"))
    )
    (net (code "94") (name "unconnected-(JP2-Pad5)") (class "Default")
      (node (ref "JP2") (pin "5") (pinfunction "5_5") (pintype "passive"))
    )
    (net (code "95") (name "unconnected-(U$1-A8-Pad32)") (class "Default")
      (node (ref "U$1") (pin "32") (pinfunction "A8_32") (pintype "output"))
    )
    (net (code "96") (name "unconnected-(U$1-A9-Pad33)") (class "Default")
      (node (ref "U$1") (pin "33") (pinfunction "A9_33") (pintype "output"))
    )
    (net (code "97") (name "unconnected-(U$1-A10-Pad34)") (class "Default")
      (node (ref "U$1") (pin "34") (pinfunction "A10_34") (pintype "output"))
    )
    (net (code "98") (name "unconnected-(U$1-A11-Pad23)") (class "Default")
      (node (ref "U$1") (pin "23") (pinfunction "A11_23") (pintype "output"))
    )
    (net (code "99") (name "unconnected-(U$1-COLOR-Pad14)") (class "Default")
      (node (ref "U$1") (pin "14") (pinfunction "COLOR_14") (pintype "output"))
    )
    (net (code "100") (name "unconnected-(U$3-NC-Pad1)") (class "Default")
      (node (ref "U$3") (pin "1") (pinfunction "NC_1") (pintype "bidirectional"))
    )
    (net (code "101") (name "unconnected-(U$4-NC-Pad1)") (class "Default")
      (node (ref "U$4") (pin "1") (pinfunction "NC_1") (pintype "no_connect"))
    )
  )
)
